# M4-Comprator.net
KiCad netlist of a schematic drawn in Altium Designer
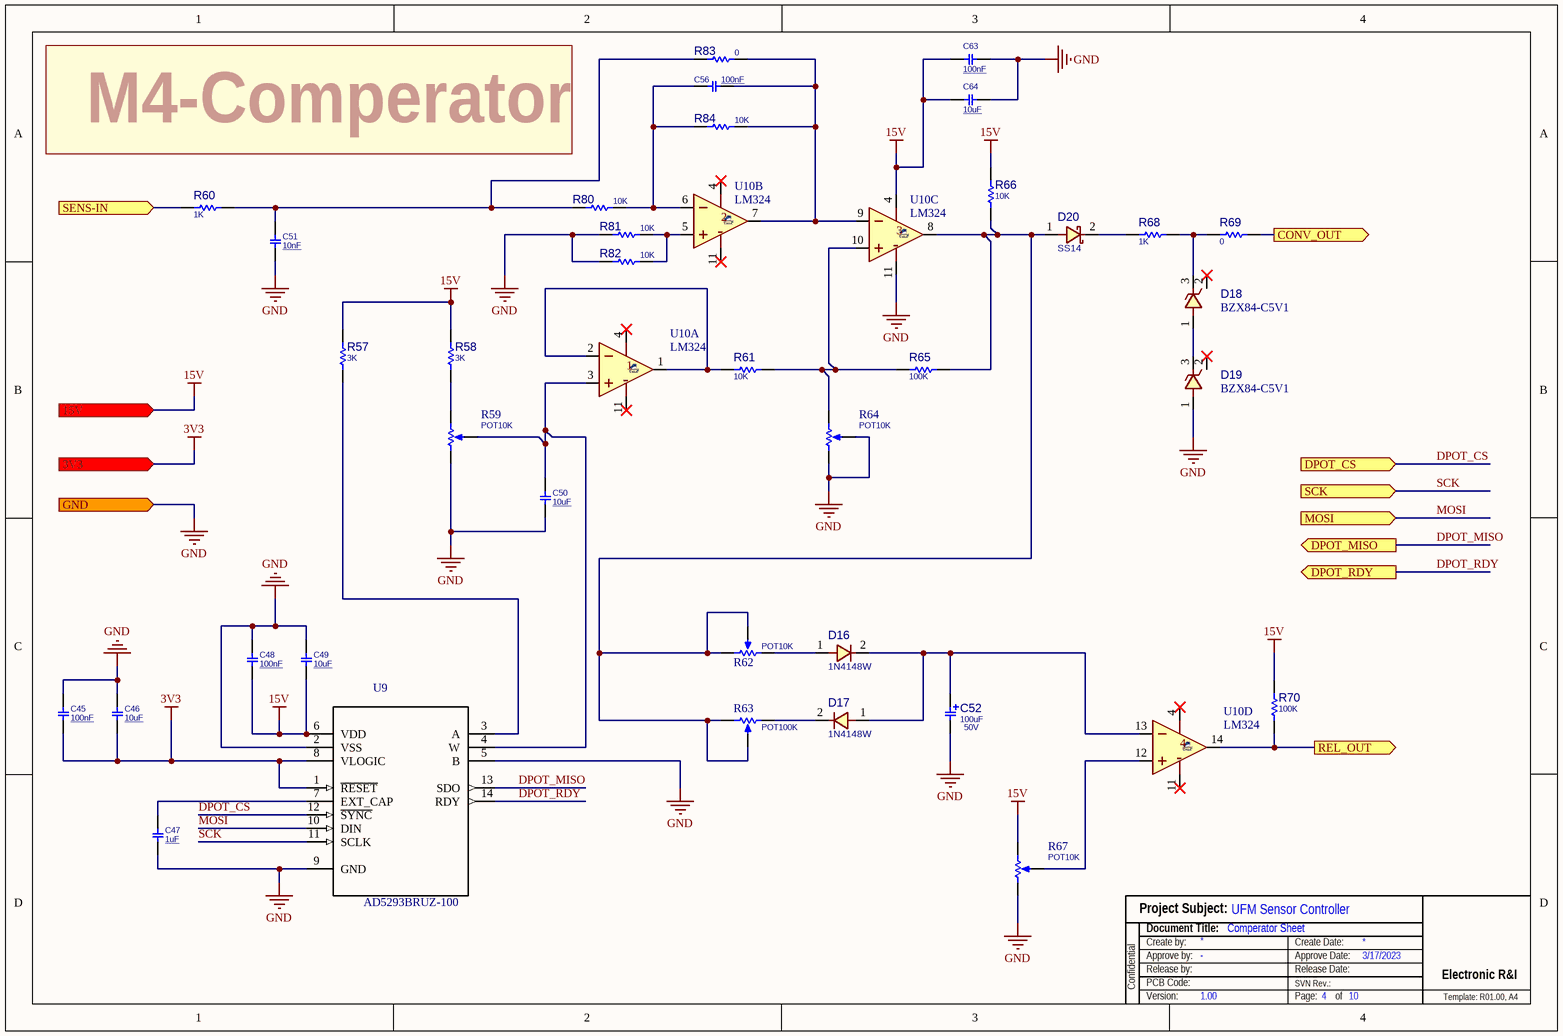
[diagram p0: M4-Comprator.SchDoc]

(export (version "E")
  (design (tool "Eeschema 10.0.6"))
  (components
    (comp (ref "C45")
      (value "100nF")
      (footprint "C1206")
      (description "CAP, MLCC, 1nF, 50V, C0G, 10%, 0402")
      (fields (field (name "MANF_P#") "MANF_PART#") (field (name "MANF") "Murata"))
      (libsource (lib "passive_smd") (part "CAP_SMD_MLCC"))
    )
    (comp (ref "C46")
      (value "10uF")
      (footprint "C1206")
      (description "CAP, MLCC, 1nF, 50V, C0G, 10%, 0402")
      (fields (field (name "MANF_P#") "MANF_PART#") (field (name "MANF") "Murata"))
      (libsource (lib "passive_smd") (part "CAP_SMD_MLCC"))
    )
    (comp (ref "C47")
      (value "1uF")
      (footprint "C1206")
      (description "CAP, MLCC, 1nF, 50V, C0G, 10%, 0402")
      (fields (field (name "MANF_P#") "MANF_PART#") (field (name "MANF") "Murata"))
      (libsource (lib "passive_smd") (part "CAP_SMD_MLCC"))
    )
    (comp (ref "C48")
      (value "100nF")
      (footprint "C1206")
      (description "CAP, MLCC, 1nF, 50V, C0G, 10%, 0402")
      (fields (field (name "MANF_P#") "MANF_PART#") (field (name "MANF") "Murata"))
      (libsource (lib "passive_smd") (part "CAP_SMD_MLCC"))
    )
    (comp (ref "C49")
      (value "10uF")
      (footprint "C1206")
      (description "CAP, MLCC, 1nF, 50V, C0G, 10%, 0402")
      (fields (field (name "MANF_P#") "MANF_PART#") (field (name "MANF") "Murata"))
      (libsource (lib "passive_smd") (part "CAP_SMD_MLCC"))
    )
    (comp (ref "C50")
      (value "10uF")
      (footprint "C1206")
      (description "CAP, MLCC, 1nF, 50V, C0G, 10%, 0402")
      (fields (field (name "MANF_P#") "MANF_PART#") (field (name "MANF") "Murata"))
      (libsource (lib "passive_smd") (part "CAP_SMD_MLCC"))
    )
    (comp (ref "C51")
      (value "10nF")
      (footprint "C1206")
      (description "CAP, MLCC, 1nF, 50V, C0G, 10%, 0402")
      (fields (field (name "MANF_P#") "MANF_PART#") (field (name "MANF") "Murata"))
      (libsource (lib "passive_smd") (part "CAP_SMD_MLCC"))
    )
    (comp (ref "C52")
      (value "100uF")
      (footprint "C_EL_8")
      (description "CAP, THD, ELEC,")
      (fields
        (field (name "MANF_P#") "MANF_PART#")
        (field (name "PARAM2") "50V")
        (field (name "MANF") "MANF")
      )
      (libsource (lib "passive_smd") (part "CAP_SMD_EL"))
    )
    (comp (ref "C56")
      (value "100nF")
      (footprint "C1206")
      (description "CAP, MLCC, 1nF, 50V, C0G, 10%, 0402")
      (fields (field (name "MANF_P#") "MANF_PART#") (field (name "MANF") "Murata"))
      (libsource (lib "passive_smd") (part "CAP_SMD_MLCC"))
    )
    (comp (ref "C63")
      (value "100nF")
      (footprint "C1206")
      (description "CAP, MLCC, 1nF, 50V, C0G, 10%, 0402")
      (fields (field (name "MANF_P#") "MANF_PART#") (field (name "MANF") "Murata"))
      (libsource (lib "passive_smd") (part "CAP_SMD_MLCC"))
    )
    (comp (ref "C64")
      (value "10uF")
      (footprint "C1206")
      (description "CAP, MLCC, 1nF, 50V, C0G, 10%, 0402")
      (fields (field (name "MANF_P#") "MANF_PART#") (field (name "MANF") "Murata"))
      (libsource (lib "passive_smd") (part "CAP_SMD_MLCC"))
    )
    (comp (ref "D16")
      (value "1N4148W")
      (footprint "D_SOD123W")
      (description "DIODE, FAST SWTICHING, 0.3A, 0.5W")
      (fields (field (name "MANF") "MANF") (field (name "MANF_P#") "1N4148"))
      (libsource (lib "diode") (part "DIODE_SMD_1N4148_SOD80"))
    )
    (comp (ref "D17")
      (value "1N4148W")
      (footprint "D_SOD123W")
      (description "DIODE, FAST SWTICHING, 0.3A, 0.5W")
      (fields (field (name "MANF") "MANF") (field (name "MANF_P#") "1N4148"))
      (libsource (lib "diode") (part "DIODE_SMD_1N4148_SOD80"))
    )
    (comp (ref "D18")
      (value "ZENER2V4")
      (footprint "SOT23_3")
      (description "DIODE, ZENER, 0.25W, 2.4V")
      (fields (field (name "MANF") "NXP") (field (name "MANF_P#") "BZX84-C5V1"))
      (libsource (lib "diode") (part "DIODE_SMD_ZENER_BZX84-C2V4"))
    )
    (comp (ref "D19")
      (value "ZENER2V4")
      (footprint "SOT23_3")
      (description "DIODE, ZENER, 0.25W, 2.4V")
      (fields (field (name "MANF") "NXP") (field (name "MANF_P#") "BZX84-C5V1"))
      (libsource (lib "diode") (part "DIODE_SMD_ZENER_BZX84-C2V4"))
    )
    (comp (ref "D20")
      (value "SS14")
      (footprint "D_SMB")
      (description "DIODE, SCHOTTKY, 40V, 1A")
      (fields (field (name "MANF") "Vishay") (field (name "MANF_P#") "SS14-E3"))
      (libsource (lib "diode") (part "DIODE_SMD_SCHOTTKY_SS14"))
    )
    (comp (ref "R57")
      (value "3K")
      (footprint "R1206")
      (description "RESISTOR, SMD")
      (libsource (lib "passive_smd") (part "RES_SMD"))
    )
    (comp (ref "R58")
      (value "3K")
      (footprint "R1206")
      (description "RESISTOR, SMD")
      (libsource (lib "passive_smd") (part "RES_SMD"))
    )
    (comp (ref "R59")
      (value "POT10K")
      (footprint "POT_3296W")
      (description "RESISTOR, THD, Potentiometer")
      (libsource (lib "resistor_pot_trimmer") (part "RES_THD_POT_3296W"))
    )
    (comp (ref "R60")
      (value "1K")
      (footprint "R1206")
      (description "RESISTOR, SMD")
      (libsource (lib "passive_smd") (part "RES_SMD"))
    )
    (comp (ref "R61")
      (value "10K")
      (footprint "R1206")
      (description "RESISTOR, SMD")
      (libsource (lib "passive_smd") (part "RES_SMD"))
    )
    (comp (ref "R62")
      (value "POT10K")
      (footprint "POT_3296W")
      (description "RESISTOR, THD, Potentiometer")
      (libsource (lib "resistor_pot_trimmer") (part "RES_THD_POT_3296W"))
    )
    (comp (ref "R63")
      (value "POT100K")
      (footprint "POT_3296W")
      (description "RESISTOR, THD, Potentiometer")
      (libsource (lib "resistor_pot_trimmer") (part "RES_THD_POT_3296W"))
    )
    (comp (ref "R64")
      (value "POT10K")
      (footprint "POT_3296W")
      (description "RESISTOR, THD, Potentiometer")
      (libsource (lib "resistor_pot_trimmer") (part "RES_THD_POT_3296W"))
    )
    (comp (ref "R65")
      (value "100K")
      (footprint "R1206")
      (description "RESISTOR, SMD")
      (libsource (lib "passive_smd") (part "RES_SMD"))
    )
    (comp (ref "R66")
      (value "10K")
      (footprint "R1206")
      (description "RESISTOR, SMD")
      (libsource (lib "passive_smd") (part "RES_SMD"))
    )
    (comp (ref "R67")
      (value "POT10K")
      (footprint "POT_3296W")
      (description "RESISTOR, THD, Potentiometer")
      (libsource (lib "resistor_pot_trimmer") (part "RES_THD_POT_3296W"))
    )
    (comp (ref "R68")
      (value "1K")
      (footprint "R1206")
      (description "RESISTOR, SMD")
      (libsource (lib "passive_smd") (part "RES_SMD"))
    )
    (comp (ref "R69")
      (value "0")
      (footprint "R1206")
      (description "RESISTOR, SMD")
      (libsource (lib "passive_smd") (part "RES_SMD"))
    )
    (comp (ref "R70")
      (value "100K")
      (footprint "R1206")
      (description "RESISTOR, SMD")
      (libsource (lib "passive_smd") (part "RES_SMD"))
    )
    (comp (ref "R80")
      (value "10K")
      (footprint "R1206")
      (description "RESISTOR, SMD")
      (libsource (lib "passive_smd") (part "RES_SMD"))
    )
    (comp (ref "R81")
      (value "10K")
      (footprint "R1206")
      (description "RESISTOR, SMD")
      (libsource (lib "passive_smd") (part "RES_SMD"))
    )
    (comp (ref "R82")
      (value "10K")
      (footprint "R1206")
      (description "RESISTOR, SMD")
      (libsource (lib "passive_smd") (part "RES_SMD"))
    )
    (comp (ref "R83")
      (value "0")
      (footprint "R1206")
      (description "RESISTOR, SMD")
      (libsource (lib "passive_smd") (part "RES_SMD"))
    )
    (comp (ref "R84")
      (value "10K")
      (footprint "R1206")
      (description "RESISTOR, SMD")
      (libsource (lib "passive_smd") (part "RES_SMD"))
    )
    (comp (ref "U9")
      (value "AD5293BRUZ-100")
      (footprint "RU_14_ADI")
      (description "Digital Potentiometer 100k Ohm 1 Circuit 1024 Taps SPI Interface 14-TSSOP")
      (fields (field (name "MF") "Analog Devices"))
      (libsource (lib "AD5293BRUZ-100") (part "AD5293BRUZ-100"))
    )
    (comp (ref "U10")
      (value "LM324")
      (footprint "SO_14")
      (description "AMP, Quad, Single-Supply")
      (fields (field (name "MANF") "ON, Texas Instruments, ST") (field (name "MANF_P#") "LM324AD"))
      (libsource (lib "amp") (part "LM324_SOP14"))
    )
  )
  (nets
    (net (code "1") (name "/CONV_OUT") (class "Default")
      (node (ref "R69") (pin "2") (pinfunction "2_2") (pintype "passive"))
    )
    (net (code "2") (name "/DPOT_CS") (class "Default")
      (node (ref "U9") (pin "12") (pinfunction "~{SYNC}_12") (pintype "input"))
    )
    (net (code "3") (name "/DPOT_MISO") (class "Default")
      (node (ref "U9") (pin "13") (pinfunction "SDO_13") (pintype "output"))
    )
    (net (code "4") (name "/DPOT_RDY") (class "Default")
      (node (ref "U9") (pin "14") (pinfunction "RDY_14") (pintype "output"))
    )
    (net (code "5") (name "/MOSI") (class "Default")
      (node (ref "U9") (pin "10") (pinfunction "DIN_10") (pintype "input"))
    )
    (net (code "6") (name "/REL_OUT") (class "Default")
      (node (ref "R70") (pin "1") (pinfunction "1_1") (pintype "passive"))
      (node (ref "U10") (pin "14") (pinfunction "OUT_14") (pintype "passive"))
    )
    (net (code "7") (name "/SCK") (class "Default")
      (node (ref "U9") (pin "11") (pinfunction "SCLK_11") (pintype "input"))
    )
    (net (code "8") (name "/SENS-IN") (class "Default")
      (node (ref "R60") (pin "1") (pinfunction "1_1") (pintype "passive"))
    )
    (net (code "9") (name "3V3") (class "Default")
      (node (ref "C45") (pin "1") (pinfunction "1_1") (pintype "passive"))
      (node (ref "C46") (pin "1") (pinfunction "1_1") (pintype "passive"))
      (node (ref "U9") (pin "1") (pinfunction "~{RESET}_1") (pintype "input"))
      (node (ref "U9") (pin "8") (pinfunction "VLOGIC_8") (pintype "power_in"))
    )
    (net (code "10") (name "15V") (class "Default")
      (node (ref "C48") (pin "1") (pinfunction "1_1") (pintype "passive"))
      (node (ref "C49") (pin "1") (pinfunction "1_1") (pintype "passive"))
      (node (ref "C63") (pin "1") (pinfunction "1_1") (pintype "passive"))
      (node (ref "C64") (pin "1") (pinfunction "1_1") (pintype "passive"))
      (node (ref "R57") (pin "2") (pinfunction "2_2") (pintype "passive"))
      (node (ref "R58") (pin "2") (pinfunction "2_2") (pintype "passive"))
      (node (ref "R66") (pin "2") (pinfunction "2_2") (pintype "passive"))
      (node (ref "R67") (pin "3") (pinfunction "BOT_3") (pintype "passive"))
      (node (ref "R70") (pin "2") (pinfunction "2_2") (pintype "passive"))
      (node (ref "U10") (pin "4") (pinfunction "V+_4") (pintype "passive"))
      (node (ref "U9") (pin "6") (pinfunction "VDD_6") (pintype "power_in"))
    )
    (net (code "11") (name "GND") (class "Default")
      (node (ref "C45") (pin "2") (pinfunction "2_2") (pintype "passive"))
      (node (ref "C46") (pin "2") (pinfunction "2_2") (pintype "passive"))
      (node (ref "C47") (pin "1") (pinfunction "1_1") (pintype "passive"))
      (node (ref "C48") (pin "2") (pinfunction "2_2") (pintype "passive"))
      (node (ref "C49") (pin "2") (pinfunction "2_2") (pintype "passive"))
      (node (ref "C50") (pin "1") (pinfunction "1_1") (pintype "passive"))
      (node (ref "C51") (pin "1") (pinfunction "1_1") (pintype "passive"))
      (node (ref "C52") (pin "2") (pinfunction "2_2") (pintype "passive"))
      (node (ref "C63") (pin "2") (pinfunction "2_2") (pintype "passive"))
      (node (ref "C64") (pin "2") (pinfunction "2_2") (pintype "passive"))
      (node (ref "D19") (pin "1") (pinfunction "1_1") (pintype "passive"))
      (node (ref "R59") (pin "1") (pinfunction "TOP_1") (pintype "passive"))
      (node (ref "R64") (pin "1") (pinfunction "TOP_1") (pintype "passive"))
      (node (ref "R64") (pin "2") (pinfunction "TAP_2") (pintype "passive"))
      (node (ref "R67") (pin "1") (pinfunction "TOP_1") (pintype "passive"))
      (node (ref "R81") (pin "1") (pinfunction "1_1") (pintype "passive"))
      (node (ref "R82") (pin "1") (pinfunction "1_1") (pintype "passive"))
      (node (ref "U10") (pin "11") (pinfunction "V-_11") (pintype "passive"))
      (node (ref "U9") (pin "2") (pinfunction "VSS_2") (pintype "power_in"))
      (node (ref "U9") (pin "5") (pinfunction "B_5") (pintype "passive"))
      (node (ref "U9") (pin "9") (pinfunction "GND_9") (pintype "passive"))
    )
    (net (code "12") (name "Net-(C51-Pad2)") (class "Default")
      (node (ref "C51") (pin "2") (pinfunction "2_2") (pintype "passive"))
      (node (ref "R60") (pin "2") (pinfunction "2_2") (pintype "passive"))
      (node (ref "R80") (pin "1") (pinfunction "1_1") (pintype "passive"))
      (node (ref "R83") (pin "1") (pinfunction "1_1") (pintype "passive"))
    )
    (net (code "13") (name "Net-(D18-Pad1)") (class "Default")
      (node (ref "D18") (pin "1") (pinfunction "1_1") (pintype "passive"))
      (node (ref "D19") (pin "3") (pinfunction "3_3") (pintype "passive"))
    )
    (net (code "14") (name "Net-(D18-Pad3)") (class "Default")
      (node (ref "D18") (pin "3") (pinfunction "3_3") (pintype "passive"))
      (node (ref "R68") (pin "2") (pinfunction "2_2") (pintype "passive"))
      (node (ref "R69") (pin "1") (pinfunction "1_1") (pintype "passive"))
    )
    (net (code "15") (name "Net-(D20-Pad2)") (class "Default")
      (node (ref "D20") (pin "2") (pinfunction "2_2") (pintype "passive"))
      (node (ref "R68") (pin "1") (pinfunction "1_1") (pintype "passive"))
    )
    (net (code "16") (name "Net-(R59-BOT)") (class "Default")
      (node (ref "R58") (pin "1") (pinfunction "1_1") (pintype "passive"))
      (node (ref "R59") (pin "3") (pinfunction "BOT_3") (pintype "passive"))
    )
    (net (code "17") (name "Net-(R59-TAP)") (class "Default")
      (node (ref "C50") (pin "2") (pinfunction "2_2") (pintype "passive"))
      (node (ref "R59") (pin "2") (pinfunction "TAP_2") (pintype "passive"))
      (node (ref "U10") (pin "3") (pinfunction "IN+_3") (pintype "passive"))
      (node (ref "U9") (pin "4") (pinfunction "W_4") (pintype "passive"))
    )
    (net (code "18") (name "Net-(R62-BOT)") (class "Default")
      (node (ref "D20") (pin "1") (pinfunction "1_1") (pintype "passive"))
      (node (ref "R62") (pin "2") (pinfunction "TAP_2") (pintype "passive"))
      (node (ref "R62") (pin "3") (pinfunction "BOT_3") (pintype "passive"))
      (node (ref "R63") (pin "1") (pinfunction "TOP_1") (pintype "passive"))
      (node (ref "R63") (pin "2") (pinfunction "TAP_2") (pintype "passive"))
      (node (ref "R65") (pin "2") (pinfunction "2_2") (pintype "passive"))
      (node (ref "R66") (pin "1") (pinfunction "1_1") (pintype "passive"))
      (node (ref "U10") (pin "8") (pinfunction "OUT_8") (pintype "passive"))
    )
    (net (code "19") (name "Net-(R62-TOP)") (class "Default")
      (node (ref "D16") (pin "1") (pinfunction "1_1") (pintype "passive"))
      (node (ref "R62") (pin "1") (pinfunction "TOP_1") (pintype "passive"))
    )
    (net (code "20") (name "Net-(R63-BOT)") (class "Default")
      (node (ref "D17") (pin "2") (pinfunction "2_2") (pintype "passive"))
      (node (ref "R63") (pin "3") (pinfunction "BOT_3") (pintype "passive"))
    )
    (net (code "21") (name "Net-(R64-BOT)") (class "Default")
      (node (ref "R61") (pin "2") (pinfunction "2_2") (pintype "passive"))
      (node (ref "R64") (pin "3") (pinfunction "BOT_3") (pintype "passive"))
      (node (ref "R65") (pin "1") (pinfunction "1_1") (pintype "passive"))
      (node (ref "U10") (pin "10") (pinfunction "IN+_10") (pintype "passive"))
    )
    (net (code "22") (name "Net-(R67-TAP)") (class "Default")
      (node (ref "R67") (pin "2") (pinfunction "TAP_2") (pintype "passive"))
      (node (ref "U10") (pin "12") (pinfunction "IN+_12") (pintype "passive"))
    )
    (net (code "23") (name "Net-(U9-A)") (class "Default")
      (node (ref "R57") (pin "1") (pinfunction "1_1") (pintype "passive"))
      (node (ref "U9") (pin "3") (pinfunction "A_3") (pintype "passive"))
    )
    (net (code "24") (name "Net-(U9-EXT_CAP)") (class "Default")
      (node (ref "C47") (pin "2") (pinfunction "2_2") (pintype "passive"))
      (node (ref "U9") (pin "7") (pinfunction "EXT_CAP_7") (pintype "passive"))
    )
    (net (code "25") (name "Net-(U10A-IN-)") (class "Default")
      (node (ref "R61") (pin "1") (pinfunction "1_1") (pintype "passive"))
      (node (ref "U10") (pin "1") (pinfunction "OUT_1") (pintype "passive"))
      (node (ref "U10") (pin "2") (pinfunction "IN-_2") (pintype "passive"))
    )
    (net (code "26") (name "Net-(U10B-IN+)") (class "Default")
      (node (ref "R81") (pin "2") (pinfunction "2_2") (pintype "passive"))
      (node (ref "R82") (pin "2") (pinfunction "2_2") (pintype "passive"))
      (node (ref "U10") (pin "5") (pinfunction "IN+_5") (pintype "passive"))
    )
    (net (code "27") (name "Net-(U10B-IN-)") (class "Default")
      (node (ref "C56") (pin "1") (pinfunction "1_1") (pintype "passive"))
      (node (ref "R80") (pin "2") (pinfunction "2_2") (pintype "passive"))
      (node (ref "R84") (pin "1") (pinfunction "1_1") (pintype "passive"))
      (node (ref "U10") (pin "6") (pinfunction "IN-_6") (pintype "passive"))
    )
    (net (code "28") (name "Net-(U10B-OUT)") (class "Default")
      (node (ref "C56") (pin "2") (pinfunction "2_2") (pintype "passive"))
      (node (ref "R83") (pin "2") (pinfunction "2_2") (pintype "passive"))
      (node (ref "R84") (pin "2") (pinfunction "2_2") (pintype "passive"))
      (node (ref "U10") (pin "7") (pinfunction "OUT_7") (pintype "passive"))
      (node (ref "U10") (pin "9") (pinfunction "IN-_9") (pintype "passive"))
    )
    (net (code "29") (name "Net-(U10D-IN-)") (class "Default")
      (node (ref "C52") (pin "1") (pinfunction "1_1") (pintype "passive"))
      (node (ref "D16") (pin "2") (pinfunction "2_2") (pintype "passive"))
      (node (ref "D17") (pin "1") (pinfunction "1_1") (pintype "passive"))
      (node (ref "U10") (pin "13") (pinfunction "IN-_13") (pintype "passive"))
    )
    (net (code "30") (name "unconnected-(D18-Pad2)") (class "Default")
      (node (ref "D18") (pin "2") (pinfunction "2_2") (pintype "passive+no_connect"))
    )
    (net (code "31") (name "unconnected-(D19-Pad2)") (class "Default")
      (node (ref "D19") (pin "2") (pinfunction "2_2") (pintype "passive+no_connect"))
    )
    (net (code "32") (name "unconnected-(U10A-V+-Pad4)") (class "Default")
      (node (ref "U10") (pin "4") (pinfunction "V+_4") (pintype "passive+no_connect"))
    )
    (net (code "33") (name "unconnected-(U10A-V--Pad11)") (class "Default")
      (node (ref "U10") (pin "11") (pinfunction "V-_11") (pintype "passive+no_connect"))
    )
    (net (code "34") (name "unconnected-(U10B-V+-Pad4)") (class "Default")
      (node (ref "U10") (pin "4") (pinfunction "V+_4") (pintype "passive+no_connect"))
    )
    (net (code "35") (name "unconnected-(U10B-V--Pad11)") (class "Default")
      (node (ref "U10") (pin "11") (pinfunction "V-_11") (pintype "passive+no_connect"))
    )
    (net (code "36") (name "unconnected-(U10D-V+-Pad4)") (class "Default")
      (node (ref "U10") (pin "4") (pinfunction "V+_4") (pintype "passive+no_connect"))
    )
    (net (code "37") (name "unconnected-(U10D-V--Pad11)") (class "Default")
      (node (ref "U10") (pin "11") (pinfunction "V-_11") (pintype "passive+no_connect"))
    )
  )
)
